# AFE.net
KiCad netlist of a schematic drawn in Altium Designer
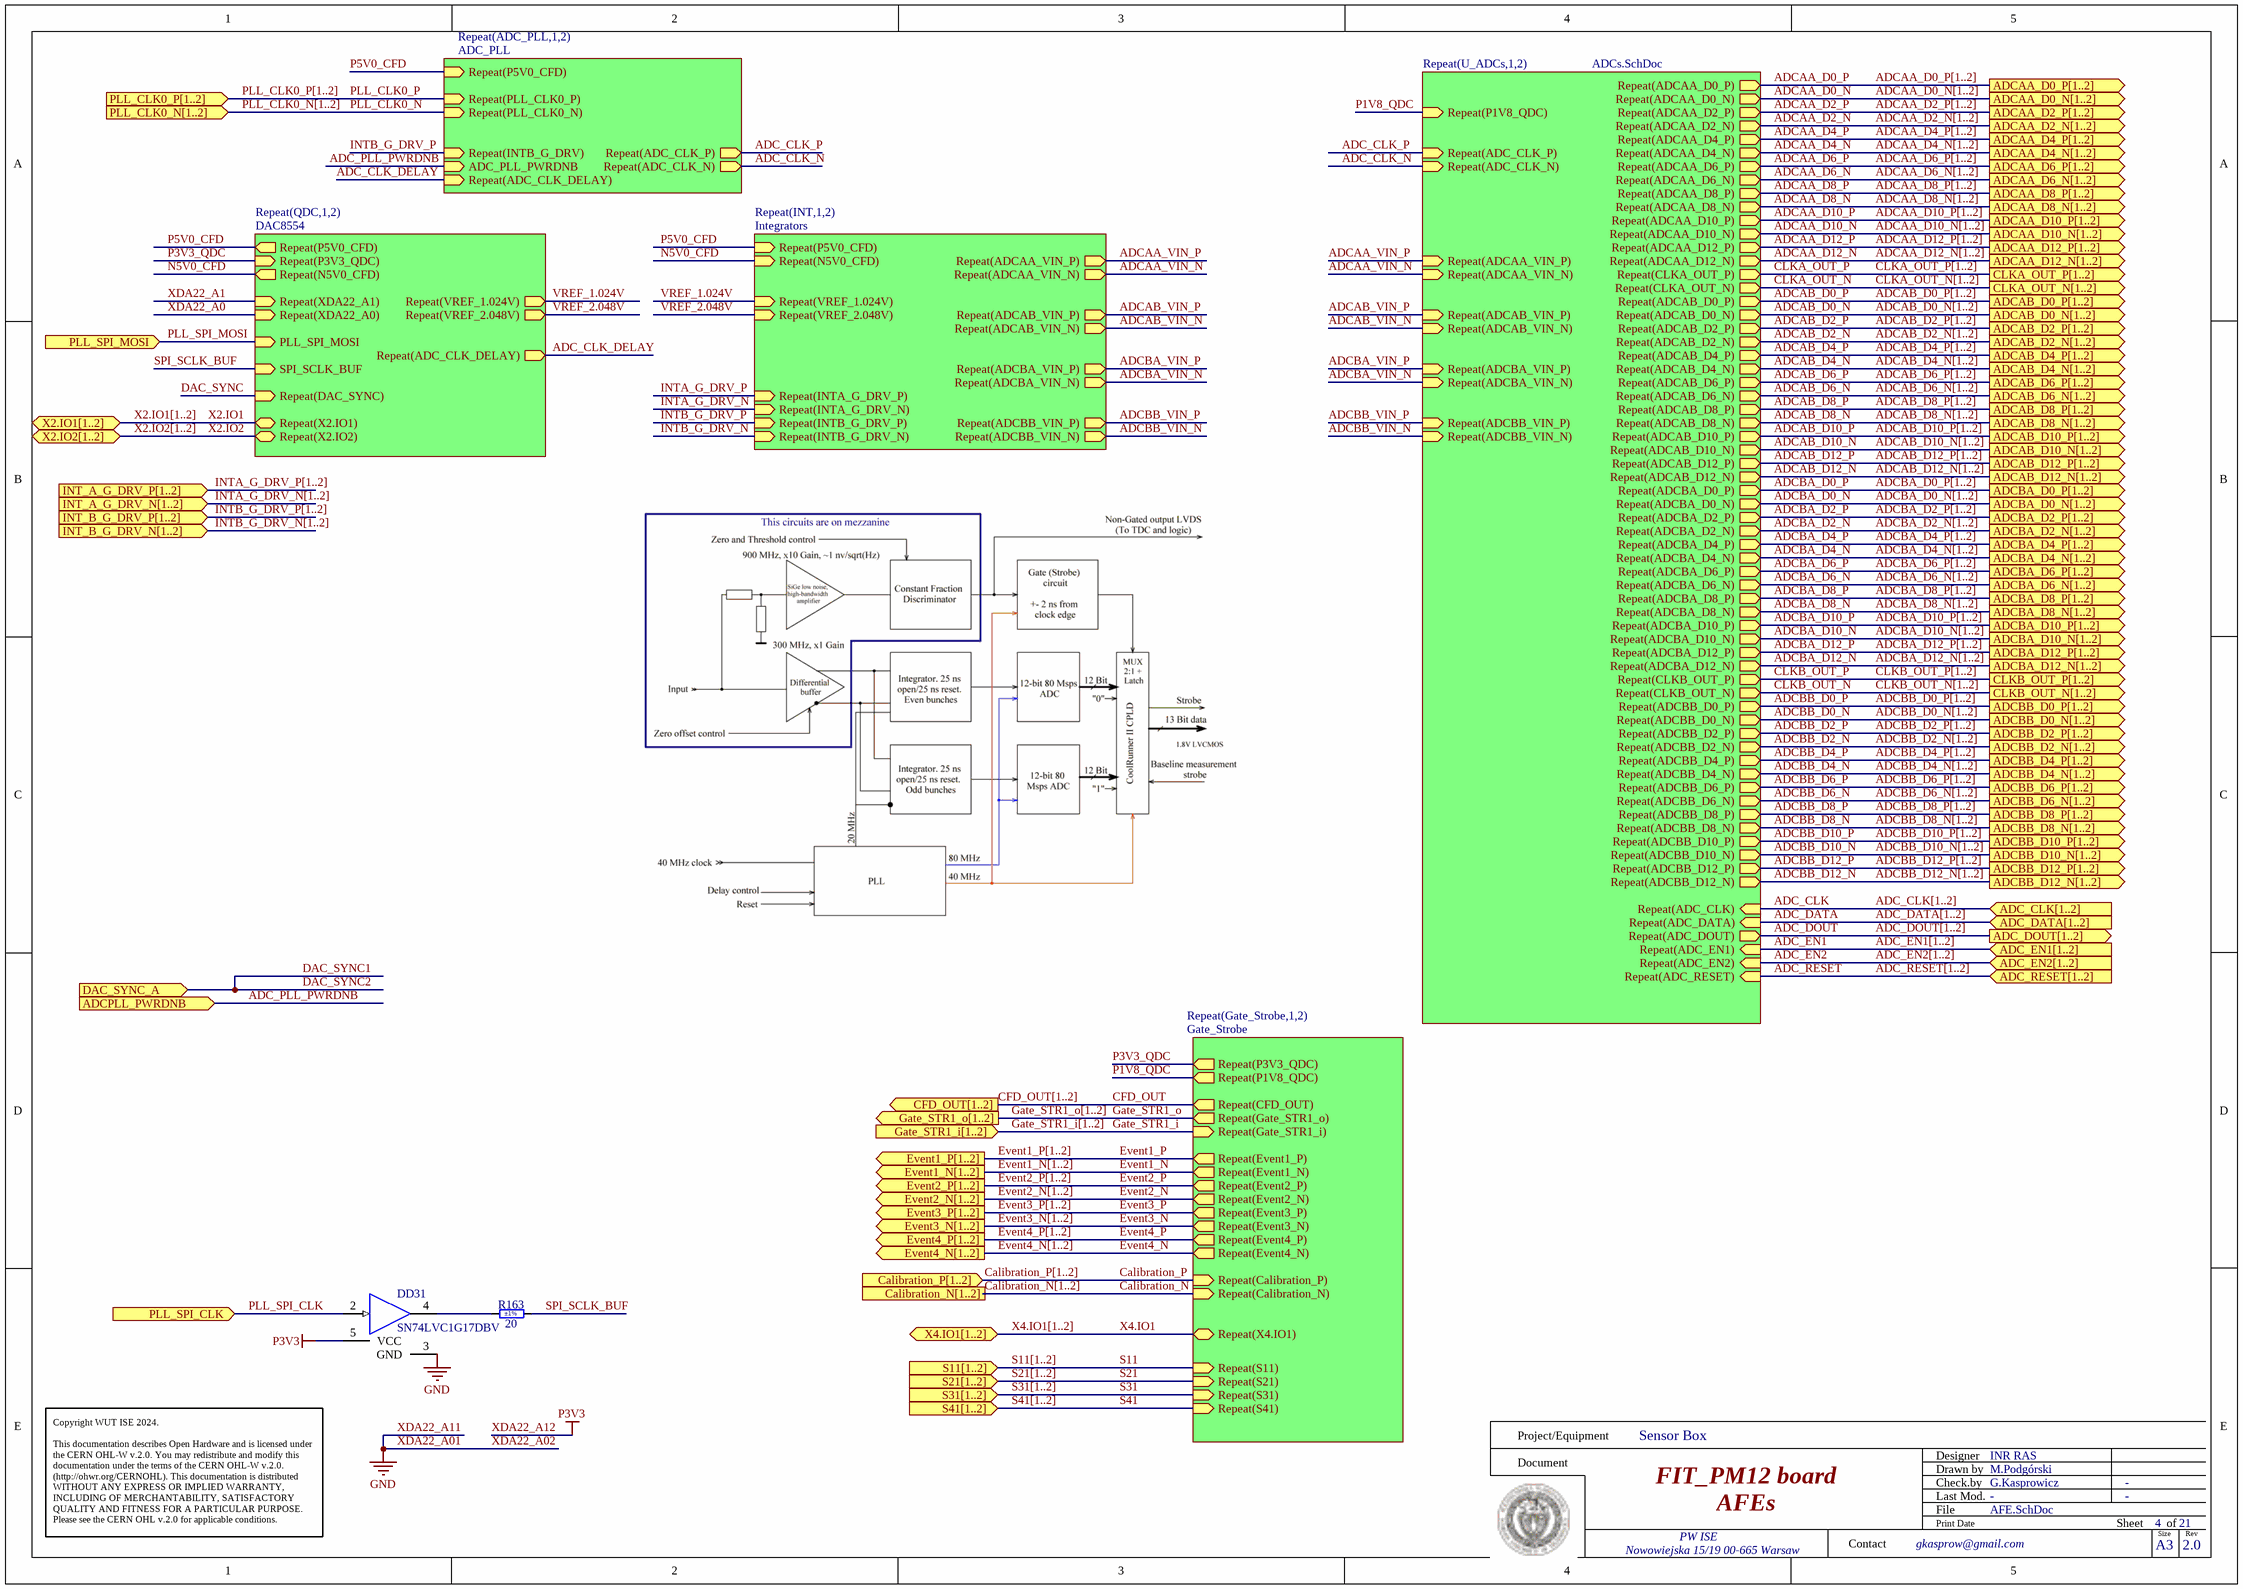
[diagram p0: AFE.SchDoc]

(export (version "E")
  (design (tool "Eeschema 10.0.6"))
  (components
    (comp (ref "DD31")
      (value "SN74LVC1G17DBV")
      (footprint "SOT95P280X145-5N")
      (description "Single Schmitt-Trigger Buffer")
      (fields
        (field (name "PART NUMBER") "SN74LVC1G17DBVR")
        (field (name "MANUFACTURER") "TEXAS INSTRUMENTS")
        (field (name "AUTHOR") "CERN DEM JLC")
      )
      (libsource (lib "ICs And Semiconductors") (part "741G17"))
    )
    (comp (ref "R163")
      (value "20")
      (footprint "RESC2012X60N")
      (description "Resistor - 1%")
      (fields
        (field (name "TOLERANCE") "±1%")
        (field (name "PART NUMBER") "R0805_20R_1%_0.125W_100PPM")
        (field (name "POWER") "0.125W")
        (field (name "AUTHOR") "CERN DEM JLC")
      )
      (libsource (lib "Resistors") (part "Resistor - 1%"))
    )
  )
  (nets
    (net (code "373") (name "/PLL_SPI_CLK") (class "Default")
      (node (ref "DD31") (pin "2") (pinfunction "IN_2") (pintype "input"))
    )
    (net (code "383") (name "/SPI_SCLK_BUF") (class "Default")
      (node (ref "R163") (pin "2") (pinfunction "2_2") (pintype "passive"))
    )
    (net (code "394") (name "GND") (class "Default")
      (node (ref "DD31") (pin "3") (pinfunction "GND_3") (pintype "power_in"))
    )
    (net (code "395") (name "Net-(DD31-OUT)") (class "Default")
      (node (ref "DD31") (pin "4") (pinfunction "OUT_4") (pintype "open_collector"))
      (node (ref "R163") (pin "1") (pinfunction "1_1") (pintype "passive"))
    )
    (net (code "396") (name "P3V3") (class "Default")
      (node (ref "DD31") (pin "5") (pinfunction "VCC_5") (pintype "power_in"))
    )
  )
)
